# CONNECTIONS.net
KiCad netlist of a schematic drawn in Altium Designer
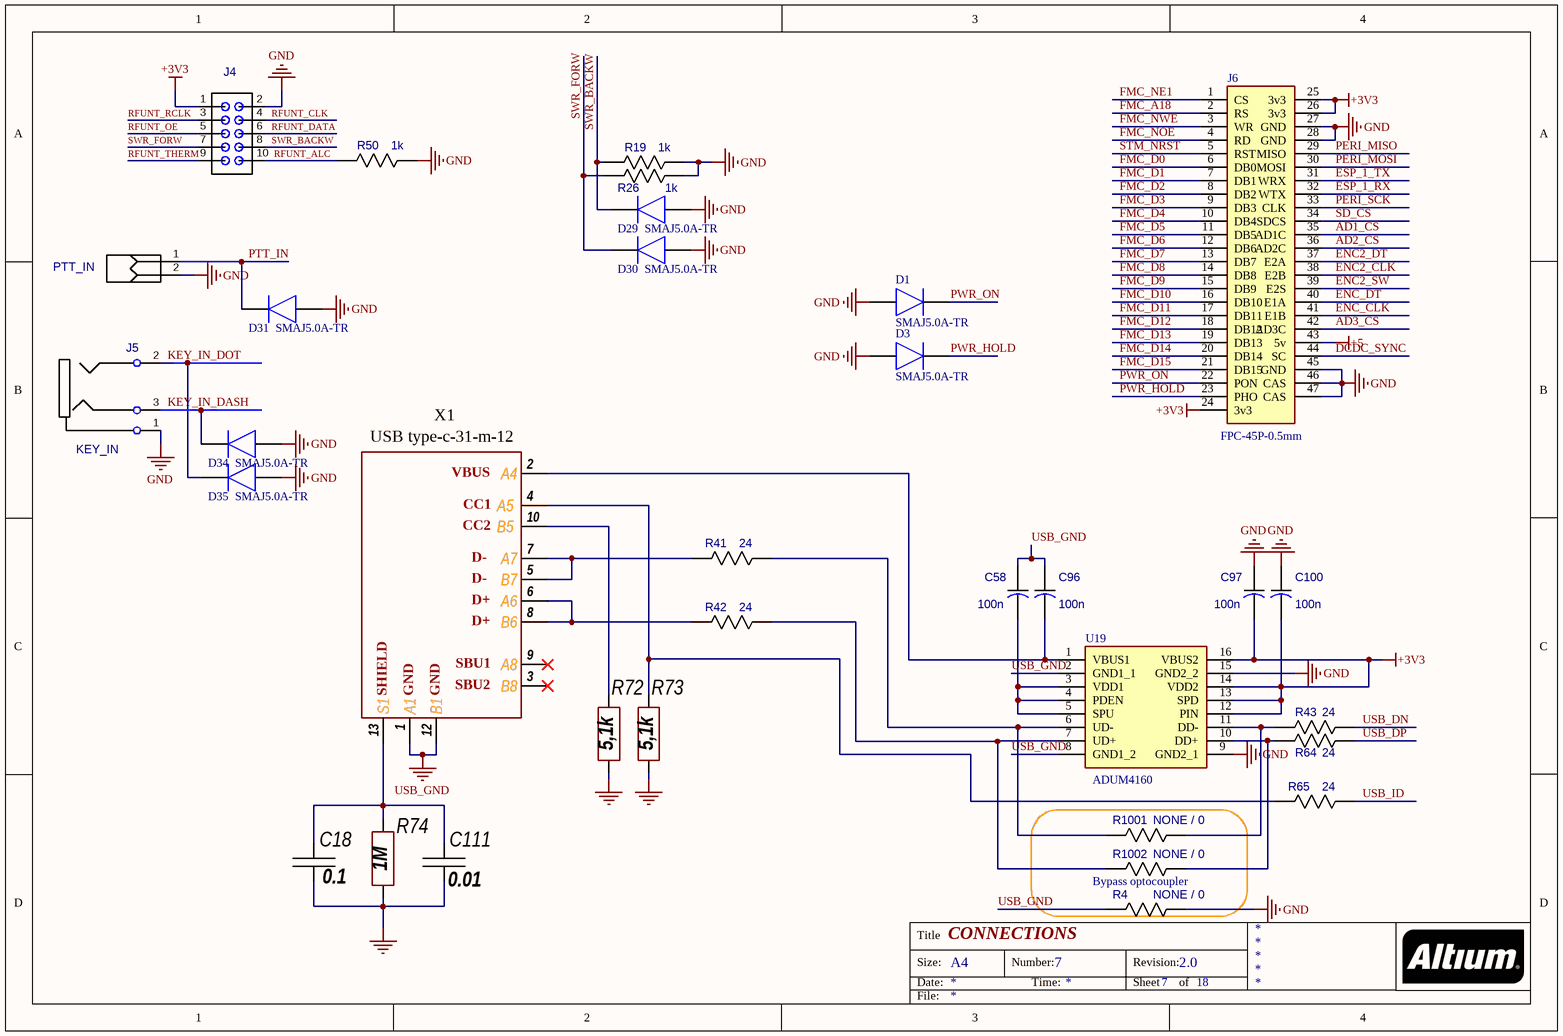
[diagram p0: CONNECTIONS.SchDoc]

(export (version "E")
  (design (tool "Eeschema 10.0.6"))
  (components
    (comp (ref "C18")
      (value "0.1")
      (footprint "standard:CH0805C")
      (libsource (lib "Discrete") (part "Capacitor"))
    )
    (comp (ref "C58")
      (value "100n")
      (footprint "CAP_0805")
      (description "CAP_0805")
      (libsource (lib "*") (part "CAP_0805"))
    )
    (comp (ref "C96")
      (value "100n")
      (footprint "CAP_0805")
      (description "CAP_0805")
      (libsource (lib "*") (part "CAP_0805"))
    )
    (comp (ref "C97")
      (value "100n")
      (footprint "CAP_0805")
      (description "CAP_0805")
      (libsource (lib "*") (part "CAP_0805"))
    )
    (comp (ref "C100")
      (value "100n")
      (footprint "CAP_0805")
      (description "CAP_0805")
      (libsource (lib "*") (part "CAP_0805"))
    )
    (comp (ref "C111")
      (value "0.01")
      (footprint "standard:CH0805C")
      (libsource (lib "Discrete") (part "Capacitor"))
    )
    (comp (ref "D1")
      (value "SMAJ5.0A-TR")
      (footprint "SMBJ36CATR")
      (description "Diode")
      (fields
        (field (name "MANUFACTURER_PART_NUMBER") "SMLVT3V3")
        (field (name "MOUSER PART NUMBER") "511-SMLVT3V3")
      )
      (libsource (lib "*") (part "SMLVT3V3"))
    )
    (comp (ref "D3")
      (value "SMAJ5.0A-TR")
      (footprint "SMBJ36CATR")
      (description "Diode")
      (fields
        (field (name "MANUFACTURER_PART_NUMBER") "SMLVT3V3")
        (field (name "MOUSER PART NUMBER") "511-SMLVT3V3")
      )
      (libsource (lib "*") (part "SMLVT3V3"))
    )
    (comp (ref "D29")
      (value "SMAJ5.0A-TR")
      (footprint "SamacSys:SMBJ36CATR")
      (description "Diode")
      (fields
        (field (name "MANUFACTURER_PART_NUMBER") "SMLVT3V3")
        (field (name "MOUSER PART NUMBER") "511-SMLVT3V3")
      )
      (libsource (lib "*") (part "SMLVT3V3"))
    )
    (comp (ref "D30")
      (value "SMAJ5.0A-TR")
      (footprint "SMBJ36CATR")
      (description "Diode")
      (fields
        (field (name "MANUFACTURER_PART_NUMBER") "SMLVT3V3")
        (field (name "MOUSER PART NUMBER") "511-SMLVT3V3")
      )
      (libsource (lib "*") (part "SMLVT3V3"))
    )
    (comp (ref "D31")
      (value "SMAJ5.0A-TR")
      (footprint "SamacSys:SMBJ36CATR")
      (description "Diode")
      (fields
        (field (name "MANUFACTURER_PART_NUMBER") "SMLVT3V3")
        (field (name "MOUSER PART NUMBER") "511-SMLVT3V3")
      )
      (libsource (lib "*") (part "SMLVT3V3"))
    )
    (comp (ref "D34")
      (value "SMAJ5.0A-TR")
      (footprint "SamacSys:SMBJ36CATR")
      (description "Diode")
      (fields
        (field (name "MANUFACTURER_PART_NUMBER") "SMLVT3V3")
        (field (name "MOUSER PART NUMBER") "511-SMLVT3V3")
      )
      (libsource (lib "*") (part "SMLVT3V3"))
    )
    (comp (ref "D35")
      (value "SMAJ5.0A-TR")
      (footprint "SamacSys:SMBJ36CATR")
      (description "Diode")
      (fields
        (field (name "MANUFACTURER_PART_NUMBER") "SMLVT3V3")
        (field (name "MOUSER PART NUMBER") "511-SMLVT3V3")
      )
      (libsource (lib "*") (part "SMLVT3V3"))
    )
    (comp (ref "J4")
      (value "~")
      (footprint "IDC10")
      (description "2*5 Pin")
      (libsource (lib "*") (part "IDC10"))
    )
    (comp (ref "J5")
      (value "KEY_IN")
      (footprint "SJ1-3525NG")
      (description "SJ1-3525NG")
      (libsource (lib "*") (part "SJ1-3523N"))
    )
    (comp (ref "J6")
      (value "FPC-45P-0.5mm")
      (footprint "MOTHERBOARD:FH12S45S05SH60")
      (description "Connector")
      (fields
        (field (name "MANUFACTURER_PART_NUMBER") "FH12S-45S-0.5SH(55)")
        (field (name "MOUSER PART NUMBER") "798-FH12S-45S-05SH55")
      )
      (libsource (lib "*") (part "FH12S-45S-0.5SH_55_"))
    )
    (comp (ref "PTT_IN")
      (value "PTT_IN")
      (footprint "51022-0200")
      (description "51022-0200")
      (libsource (lib "*") (part "51022-0200"))
    )
    (comp (ref "R4")
      (value "NONE / 0")
      (footprint "RES_0805")
      (description "RES_0805")
      (libsource (lib "*") (part "RES_0805"))
    )
    (comp (ref "R19")
      (value "1k")
      (footprint "RES_0805")
      (description "RES_0805")
      (libsource (lib "*") (part "RES_0805"))
    )
    (comp (ref "R26")
      (value "1k")
      (footprint "RES_0805")
      (description "RES_0805")
      (libsource (lib "*") (part "RES_0805"))
    )
    (comp (ref "R41")
      (value "24")
      (footprint "RES_0805")
      (description "RES_0805")
      (libsource (lib "*") (part "RES_0805"))
    )
    (comp (ref "R42")
      (value "24")
      (footprint "RES_0805")
      (description "RES_0805")
      (libsource (lib "*") (part "RES_0805"))
    )
    (comp (ref "R43")
      (value "24")
      (footprint "RES_0805")
      (description "RES_0805")
      (libsource (lib "*") (part "RES_0805"))
    )
    (comp (ref "R50")
      (value "1k")
      (footprint "RES_0805")
      (description "RES_0805")
      (libsource (lib "*") (part "RES_0805"))
    )
    (comp (ref "R64")
      (value "24")
      (footprint "RES_0805")
      (description "RES_0805")
      (libsource (lib "*") (part "RES_0805"))
    )
    (comp (ref "R65")
      (value "24")
      (footprint "RES_0805")
      (description "RES_0805")
      (libsource (lib "*") (part "RES_0805"))
    )
    (comp (ref "R72")
      (value "5,1k")
      (footprint "standard:CH0805R")
      (libsource (lib "Discrete") (part "Resistor"))
    )
    (comp (ref "R73")
      (value "5,1k")
      (footprint "standard:CH0805R")
      (libsource (lib "Discrete") (part "Resistor"))
    )
    (comp (ref "R74")
      (value "1M")
      (footprint "standard:CH0805R")
      (libsource (lib "Discrete") (part "Resistor"))
    )
    (comp (ref "R1001")
      (value "NONE / 0")
      (footprint "RES_0805")
      (description "RES_0805")
      (libsource (lib "*") (part "RES_0805"))
    )
    (comp (ref "R1002")
      (value "NONE / 0")
      (footprint "RES_0805")
      (description "RES_0805")
      (libsource (lib "*") (part "RES_0805"))
    )
    (comp (ref "U19")
      (value "ADUM4160")
      (footprint "SOIC127P1032X265-16N")
      (description "Integrated Circuit")
      (fields
        (field (name "MANUFACTURER_PART_NUMBER") "ADUM4160BRWZ")
        (field (name "MOUSER PART NUMBER") "584-ADUM4160BRWZ")
      )
      (libsource (lib "*") (part "ADUM4160BRWZ"))
    )
    (comp (ref "X1")
      (value "USB type-c-31-m-12")
      (footprint "TYPE-C-31-M-12_V1")
      (libsource (lib "Connectors") (part "USB-C_2.0"))
    )
  )
  (nets
    (net (code "1") (name "+3V3") (class "Default")
      (node (ref "C100") (pin "2") (pinfunction "2_2") (pintype "passive"))
      (node (ref "C97") (pin "2") (pinfunction "2_2") (pintype "passive"))
      (node (ref "J4") (pin "1") (pinfunction "1_1") (pintype "passive"))
      (node (ref "J6") (pin "24") (pinfunction "3v3_24") (pintype "passive"))
      (node (ref "J6") (pin "25") (pinfunction "3v3_25") (pintype "passive"))
      (node (ref "J6") (pin "26") (pinfunction "3v3_26") (pintype "passive"))
      (node (ref "U19") (pin "12") (pinfunction "PIN_12") (pintype "passive"))
      (node (ref "U19") (pin "13") (pinfunction "SPD_13") (pintype "passive"))
      (node (ref "U19") (pin "14") (pinfunction "VDD2_14") (pintype "passive"))
      (node (ref "U19") (pin "16") (pinfunction "VBUS2_16") (pintype "passive"))
    )
    (net (code "2") (name "+5") (class "Default")
      (node (ref "J6") (pin "43") (pinfunction "5v_43") (pintype "passive"))
    )
    (net (code "3") (name "/AD1_CS") (class "Default")
      (node (ref "J6") (pin "35") (pinfunction "AD1C_35") (pintype "passive"))
    )
    (net (code "4") (name "/AD2_CS") (class "Default")
      (node (ref "J6") (pin "36") (pinfunction "AD2C_36") (pintype "passive"))
    )
    (net (code "5") (name "/AD3_CS") (class "Default")
      (node (ref "J6") (pin "42") (pinfunction "AD3C_42") (pintype "passive"))
    )
    (net (code "6") (name "/DCDC_SYNC") (class "Default")
      (node (ref "J6") (pin "44") (pinfunction "SC_44") (pintype "passive"))
    )
    (net (code "7") (name "/ENC2_CLK") (class "Default")
      (node (ref "J6") (pin "38") (pinfunction "E2B_38") (pintype "passive"))
    )
    (net (code "8") (name "/ENC2_DT") (class "Default")
      (node (ref "J6") (pin "37") (pinfunction "E2A_37") (pintype "passive"))
    )
    (net (code "9") (name "/ENC2_SW") (class "Default")
      (node (ref "J6") (pin "39") (pinfunction "E2S_39") (pintype "passive"))
    )
    (net (code "10") (name "/ENC_CLK") (class "Default")
      (node (ref "J6") (pin "41") (pinfunction "E1B_41") (pintype "passive"))
    )
    (net (code "11") (name "/ENC_DT") (class "Default")
      (node (ref "J6") (pin "40") (pinfunction "E1A_40") (pintype "passive"))
    )
    (net (code "12") (name "/ESP_1_RX") (class "Default")
      (node (ref "J6") (pin "32") (pinfunction "WTX_32") (pintype "passive"))
    )
    (net (code "13") (name "/ESP_1_TX") (class "Default")
      (node (ref "J6") (pin "31") (pinfunction "WRX_31") (pintype "passive"))
    )
    (net (code "14") (name "/FMC_A18") (class "Default")
      (node (ref "J6") (pin "2") (pinfunction "RS_2") (pintype "passive"))
    )
    (net (code "15") (name "/FMC_D0") (class "Default")
      (node (ref "J6") (pin "6") (pinfunction "DB0_6") (pintype "passive"))
    )
    (net (code "16") (name "/FMC_D1") (class "Default")
      (node (ref "J6") (pin "7") (pinfunction "DB1_7") (pintype "passive"))
    )
    (net (code "17") (name "/FMC_D2") (class "Default")
      (node (ref "J6") (pin "8") (pinfunction "DB2_8") (pintype "passive"))
    )
    (net (code "18") (name "/FMC_D3") (class "Default")
      (node (ref "J6") (pin "9") (pinfunction "DB3_9") (pintype "passive"))
    )
    (net (code "19") (name "/FMC_D4") (class "Default")
      (node (ref "J6") (pin "10") (pinfunction "DB4_10") (pintype "passive"))
    )
    (net (code "20") (name "/FMC_D5") (class "Default")
      (node (ref "J6") (pin "11") (pinfunction "DB5_11") (pintype "passive"))
    )
    (net (code "21") (name "/FMC_D6") (class "Default")
      (node (ref "J6") (pin "12") (pinfunction "DB6_12") (pintype "passive"))
    )
    (net (code "22") (name "/FMC_D7") (class "Default")
      (node (ref "J6") (pin "13") (pinfunction "DB7_13") (pintype "passive"))
    )
    (net (code "23") (name "/FMC_D8") (class "Default")
      (node (ref "J6") (pin "14") (pinfunction "DB8_14") (pintype "passive"))
    )
    (net (code "24") (name "/FMC_D9") (class "Default")
      (node (ref "J6") (pin "15") (pinfunction "DB9_15") (pintype "passive"))
    )
    (net (code "25") (name "/FMC_D10") (class "Default")
      (node (ref "J6") (pin "16") (pinfunction "DB10_16") (pintype "passive"))
    )
    (net (code "26") (name "/FMC_D11") (class "Default")
      (node (ref "J6") (pin "17") (pinfunction "DB11_17") (pintype "passive"))
    )
    (net (code "27") (name "/FMC_D12") (class "Default")
      (node (ref "J6") (pin "18") (pinfunction "DB12_18") (pintype "passive"))
    )
    (net (code "28") (name "/FMC_D13") (class "Default")
      (node (ref "J6") (pin "19") (pinfunction "DB13_19") (pintype "passive"))
    )
    (net (code "29") (name "/FMC_D14") (class "Default")
      (node (ref "J6") (pin "20") (pinfunction "DB14_20") (pintype "passive"))
    )
    (net (code "30") (name "/FMC_D15") (class "Default")
      (node (ref "J6") (pin "21") (pinfunction "DB15_21") (pintype "passive"))
    )
    (net (code "31") (name "/FMC_NE1") (class "Default")
      (node (ref "J6") (pin "1") (pinfunction "CS_1") (pintype "passive"))
    )
    (net (code "32") (name "/FMC_NOE") (class "Default")
      (node (ref "J6") (pin "4") (pinfunction "RD_4") (pintype "passive"))
    )
    (net (code "33") (name "/FMC_NWE") (class "Default")
      (node (ref "J6") (pin "3") (pinfunction "WR_3") (pintype "passive"))
    )
    (net (code "34") (name "/KEY_IN_DASH") (class "Default")
      (node (ref "D34") (pin "1") (pinfunction "K_1") (pintype "passive"))
      (node (ref "J5") (pin "3") (pinfunction "ring_3") (pintype "passive"))
    )
    (net (code "35") (name "/KEY_IN_DOT") (class "Default")
      (node (ref "D35") (pin "1") (pinfunction "K_1") (pintype "passive"))
      (node (ref "J5") (pin "2") (pinfunction "tip_2") (pintype "passive"))
    )
    (net (code "36") (name "/PERI_MISO") (class "Default")
      (node (ref "J6") (pin "29") (pinfunction "MISO_29") (pintype "passive"))
    )
    (net (code "37") (name "/PERI_MOSI") (class "Default")
      (node (ref "J6") (pin "30") (pinfunction "MOSI_30") (pintype "passive"))
    )
    (net (code "38") (name "/PERI_SCK") (class "Default")
      (node (ref "J6") (pin "33") (pinfunction "CLK_33") (pintype "passive"))
    )
    (net (code "39") (name "/PTT_IN") (class "Default")
      (node (ref "D31") (pin "1") (pinfunction "K_1") (pintype "passive"))
      (node (ref "PTT_IN") (pin "1") (pinfunction "1_1") (pintype "passive"))
    )
    (net (code "40") (name "/PWR_HOLD") (class "Default")
      (node (ref "D3") (pin "1") (pinfunction "K_1") (pintype "passive"))
      (node (ref "J6") (pin "23") (pinfunction "PHO_23") (pintype "passive"))
    )
    (net (code "41") (name "/PWR_ON") (class "Default")
      (node (ref "D1") (pin "1") (pinfunction "K_1") (pintype "passive"))
      (node (ref "J6") (pin "22") (pinfunction "PON_22") (pintype "passive"))
    )
    (net (code "42") (name "/RFUNT_ALC") (class "Default")
      (node (ref "J4") (pin "10") (pinfunction "10_10") (pintype "passive"))
      (node (ref "R50") (pin "1") (pinfunction "1_1") (pintype "passive"))
    )
    (net (code "43") (name "/RFUNT_CLK") (class "Default")
      (node (ref "J4") (pin "4") (pinfunction "4_4") (pintype "passive"))
    )
    (net (code "44") (name "/RFUNT_DATA") (class "Default")
      (node (ref "J4") (pin "6") (pinfunction "6_6") (pintype "passive"))
    )
    (net (code "45") (name "/RFUNT_OE") (class "Default")
      (node (ref "J4") (pin "5") (pinfunction "5_5") (pintype "passive"))
    )
    (net (code "46") (name "/RFUNT_RCLK") (class "Default")
      (node (ref "J4") (pin "3") (pinfunction "3_3") (pintype "passive"))
    )
    (net (code "47") (name "/RFUNT_THERM") (class "Default")
      (node (ref "J4") (pin "9") (pinfunction "9_9") (pintype "passive"))
    )
    (net (code "48") (name "/SD_CS") (class "Default")
      (node (ref "J6") (pin "34") (pinfunction "SDCS_34") (pintype "passive"))
    )
    (net (code "49") (name "/STM_NRST") (class "Default")
      (node (ref "J6") (pin "5") (pinfunction "RST_5") (pintype "passive"))
    )
    (net (code "50") (name "/SWR_BACKW") (class "Default")
      (node (ref "D29") (pin "1") (pinfunction "K_1") (pintype "passive"))
      (node (ref "J4") (pin "8") (pinfunction "8_8") (pintype "passive"))
      (node (ref "R19") (pin "1") (pinfunction "1_1") (pintype "passive"))
    )
    (net (code "51") (name "/SWR_FORW") (class "Default")
      (node (ref "D30") (pin "1") (pinfunction "K_1") (pintype "passive"))
      (node (ref "J4") (pin "7") (pinfunction "7_7") (pintype "passive"))
      (node (ref "R26") (pin "1") (pinfunction "1_1") (pintype "passive"))
    )
    (net (code "52") (name "/USB_DN") (class "Default")
      (node (ref "R43") (pin "2") (pinfunction "2_2") (pintype "passive"))
    )
    (net (code "53") (name "/USB_DP") (class "Default")
      (node (ref "R64") (pin "2") (pinfunction "2_2") (pintype "passive"))
    )
    (net (code "54") (name "/USB_ID") (class "Default")
      (node (ref "R65") (pin "2") (pinfunction "2_2") (pintype "passive"))
    )
    (net (code "55") (name "GND") (class "Default")
      (node (ref "C100") (pin "1") (pinfunction "1_1") (pintype "passive"))
      (node (ref "C111") (pin "1") (pinfunction "1_1") (pintype "passive"))
      (node (ref "C18") (pin "1") (pinfunction "1_1") (pintype "passive"))
      (node (ref "C97") (pin "1") (pinfunction "1_1") (pintype "passive"))
      (node (ref "D1") (pin "2") (pinfunction "A_2") (pintype "passive"))
      (node (ref "D29") (pin "2") (pinfunction "A_2") (pintype "passive"))
      (node (ref "D3") (pin "2") (pinfunction "A_2") (pintype "passive"))
      (node (ref "D30") (pin "2") (pinfunction "A_2") (pintype "passive"))
      (node (ref "D31") (pin "2") (pinfunction "A_2") (pintype "passive"))
      (node (ref "D34") (pin "2") (pinfunction "A_2") (pintype "passive"))
      (node (ref "D35") (pin "2") (pinfunction "A_2") (pintype "passive"))
      (node (ref "J4") (pin "2") (pinfunction "2_2") (pintype "passive"))
      (node (ref "J5") (pin "1") (pinfunction "sleeve_1") (pintype "passive"))
      (node (ref "J6") (pin "27") (pinfunction "GND_27") (pintype "passive"))
      (node (ref "J6") (pin "28") (pinfunction "GND_28") (pintype "passive"))
      (node (ref "J6") (pin "45") (pinfunction "GND_45") (pintype "passive"))
      (node (ref "J6") (pin "46") (pinfunction "CAS_46") (pintype "passive"))
      (node (ref "J6") (pin "47") (pinfunction "CAS_47") (pintype "passive"))
      (node (ref "PTT_IN") (pin "2") (pinfunction "2_2") (pintype "passive"))
      (node (ref "R19") (pin "2") (pinfunction "2_2") (pintype "passive"))
      (node (ref "R26") (pin "2") (pinfunction "2_2") (pintype "passive"))
      (node (ref "R4") (pin "2") (pinfunction "2_2") (pintype "passive"))
      (node (ref "R50") (pin "2") (pinfunction "2_2") (pintype "passive"))
      (node (ref "R72") (pin "1") (pinfunction "1_1") (pintype "passive"))
      (node (ref "R73") (pin "1") (pinfunction "1_1") (pintype "passive"))
      (node (ref "R74") (pin "1") (pinfunction "1_1") (pintype "passive"))
      (node (ref "U19") (pin "15") (pinfunction "GND2_2_15") (pintype "passive"))
      (node (ref "U19") (pin "9") (pinfunction "GND2_1_9") (pintype "passive"))
    )
    (net (code "56") (name "Net-(U19-DD+)") (class "Default")
      (node (ref "R1002") (pin "2") (pinfunction "2_2") (pintype "passive"))
      (node (ref "R64") (pin "1") (pinfunction "1_1") (pintype "passive"))
      (node (ref "U19") (pin "10") (pinfunction "DD+_10") (pintype "passive"))
    )
    (net (code "57") (name "Net-(U19-DD-)") (class "Default")
      (node (ref "R1001") (pin "2") (pinfunction "2_2") (pintype "passive"))
      (node (ref "R43") (pin "1") (pinfunction "1_1") (pintype "passive"))
      (node (ref "U19") (pin "11") (pinfunction "DD-_11") (pintype "passive"))
    )
    (net (code "58") (name "Net-(U19-PDEN)") (class "Default")
      (node (ref "C58") (pin "2") (pinfunction "2_2") (pintype "passive"))
      (node (ref "U19") (pin "3") (pinfunction "VDD1_3") (pintype "passive"))
      (node (ref "U19") (pin "4") (pinfunction "PDEN_4") (pintype "passive"))
      (node (ref "U19") (pin "5") (pinfunction "SPU_5") (pintype "passive"))
    )
    (net (code "59") (name "Net-(U19-UD+)") (class "Default")
      (node (ref "R1002") (pin "1") (pinfunction "1_1") (pintype "passive"))
      (node (ref "R42") (pin "2") (pinfunction "2_2") (pintype "passive"))
      (node (ref "U19") (pin "7") (pinfunction "UD+_7") (pintype "passive"))
    )
    (net (code "60") (name "Net-(U19-UD-)") (class "Default")
      (node (ref "R1001") (pin "1") (pinfunction "1_1") (pintype "passive"))
      (node (ref "R41") (pin "2") (pinfunction "2_2") (pintype "passive"))
      (node (ref "U19") (pin "6") (pinfunction "UD-_6") (pintype "passive"))
    )
    (net (code "61") (name "Net-(U19-VBUS1)") (class "Default")
      (node (ref "C96") (pin "2") (pinfunction "2_2") (pintype "passive"))
      (node (ref "U19") (pin "1") (pinfunction "VBUS1_1") (pintype "passive"))
      (node (ref "X1") (pin "2") (pinfunction "A4_2") (pintype "power_in"))
    )
    (net (code "62") (name "Net-(X1-A5)") (class "Default")
      (node (ref "R65") (pin "1") (pinfunction "1_1") (pintype "passive"))
      (node (ref "R73") (pin "2") (pinfunction "2_2") (pintype "passive"))
      (node (ref "X1") (pin "4") (pinfunction "A5_4") (pintype "power_in"))
    )
    (net (code "63") (name "Net-(X1-A6)") (class "Default")
      (node (ref "R42") (pin "1") (pinfunction "1_1") (pintype "passive"))
      (node (ref "X1") (pin "6") (pinfunction "A6_6") (pintype "power_in"))
      (node (ref "X1") (pin "8") (pinfunction "B6_8") (pintype "power_in"))
    )
    (net (code "64") (name "Net-(X1-A7)") (class "Default")
      (node (ref "R41") (pin "1") (pinfunction "1_1") (pintype "passive"))
      (node (ref "X1") (pin "5") (pinfunction "B7_5") (pintype "power_in"))
      (node (ref "X1") (pin "7") (pinfunction "A7_7") (pintype "power_in"))
    )
    (net (code "65") (name "Net-(X1-B5)") (class "Default")
      (node (ref "R72") (pin "2") (pinfunction "2_2") (pintype "passive"))
      (node (ref "X1") (pin "10") (pinfunction "B5_10") (pintype "power_in"))
    )
    (net (code "66") (name "Net-(X1-S1)") (class "Default")
      (node (ref "C111") (pin "2") (pinfunction "2_2") (pintype "power_in"))
      (node (ref "C18") (pin "2") (pinfunction "2_2") (pintype "power_in"))
      (node (ref "R74") (pin "2") (pinfunction "2_2") (pintype "passive"))
      (node (ref "X1") (pin "13") (pinfunction "S1_13") (pintype "power_in"))
    )
    (net (code "67") (name "USB_GND") (class "Default")
      (node (ref "C58") (pin "1") (pinfunction "1_1") (pintype "passive"))
      (node (ref "C96") (pin "1") (pinfunction "1_1") (pintype "passive"))
      (node (ref "R4") (pin "1") (pinfunction "1_1") (pintype "passive"))
      (node (ref "U19") (pin "2") (pinfunction "GND1_1_2") (pintype "passive"))
      (node (ref "U19") (pin "8") (pinfunction "GND1_2_8") (pintype "passive"))
      (node (ref "X1") (pin "1") (pinfunction "A1_1") (pintype "passive"))
      (node (ref "X1") (pin "12") (pinfunction "B1_12") (pintype "passive"))
    )
    (net (code "68") (name "unconnected-(X1-A8-Pad9)") (class "Default")
      (node (ref "X1") (pin "9") (pinfunction "A8_9") (pintype "power_in+no_connect"))
    )
    (net (code "69") (name "unconnected-(X1-B8-Pad3)") (class "Default")
      (node (ref "X1") (pin "3") (pinfunction "B8_3") (pintype "power_in+no_connect"))
    )
  )
)
